# emb.net
KiCad netlist of a schematic drawn in EasyEDA
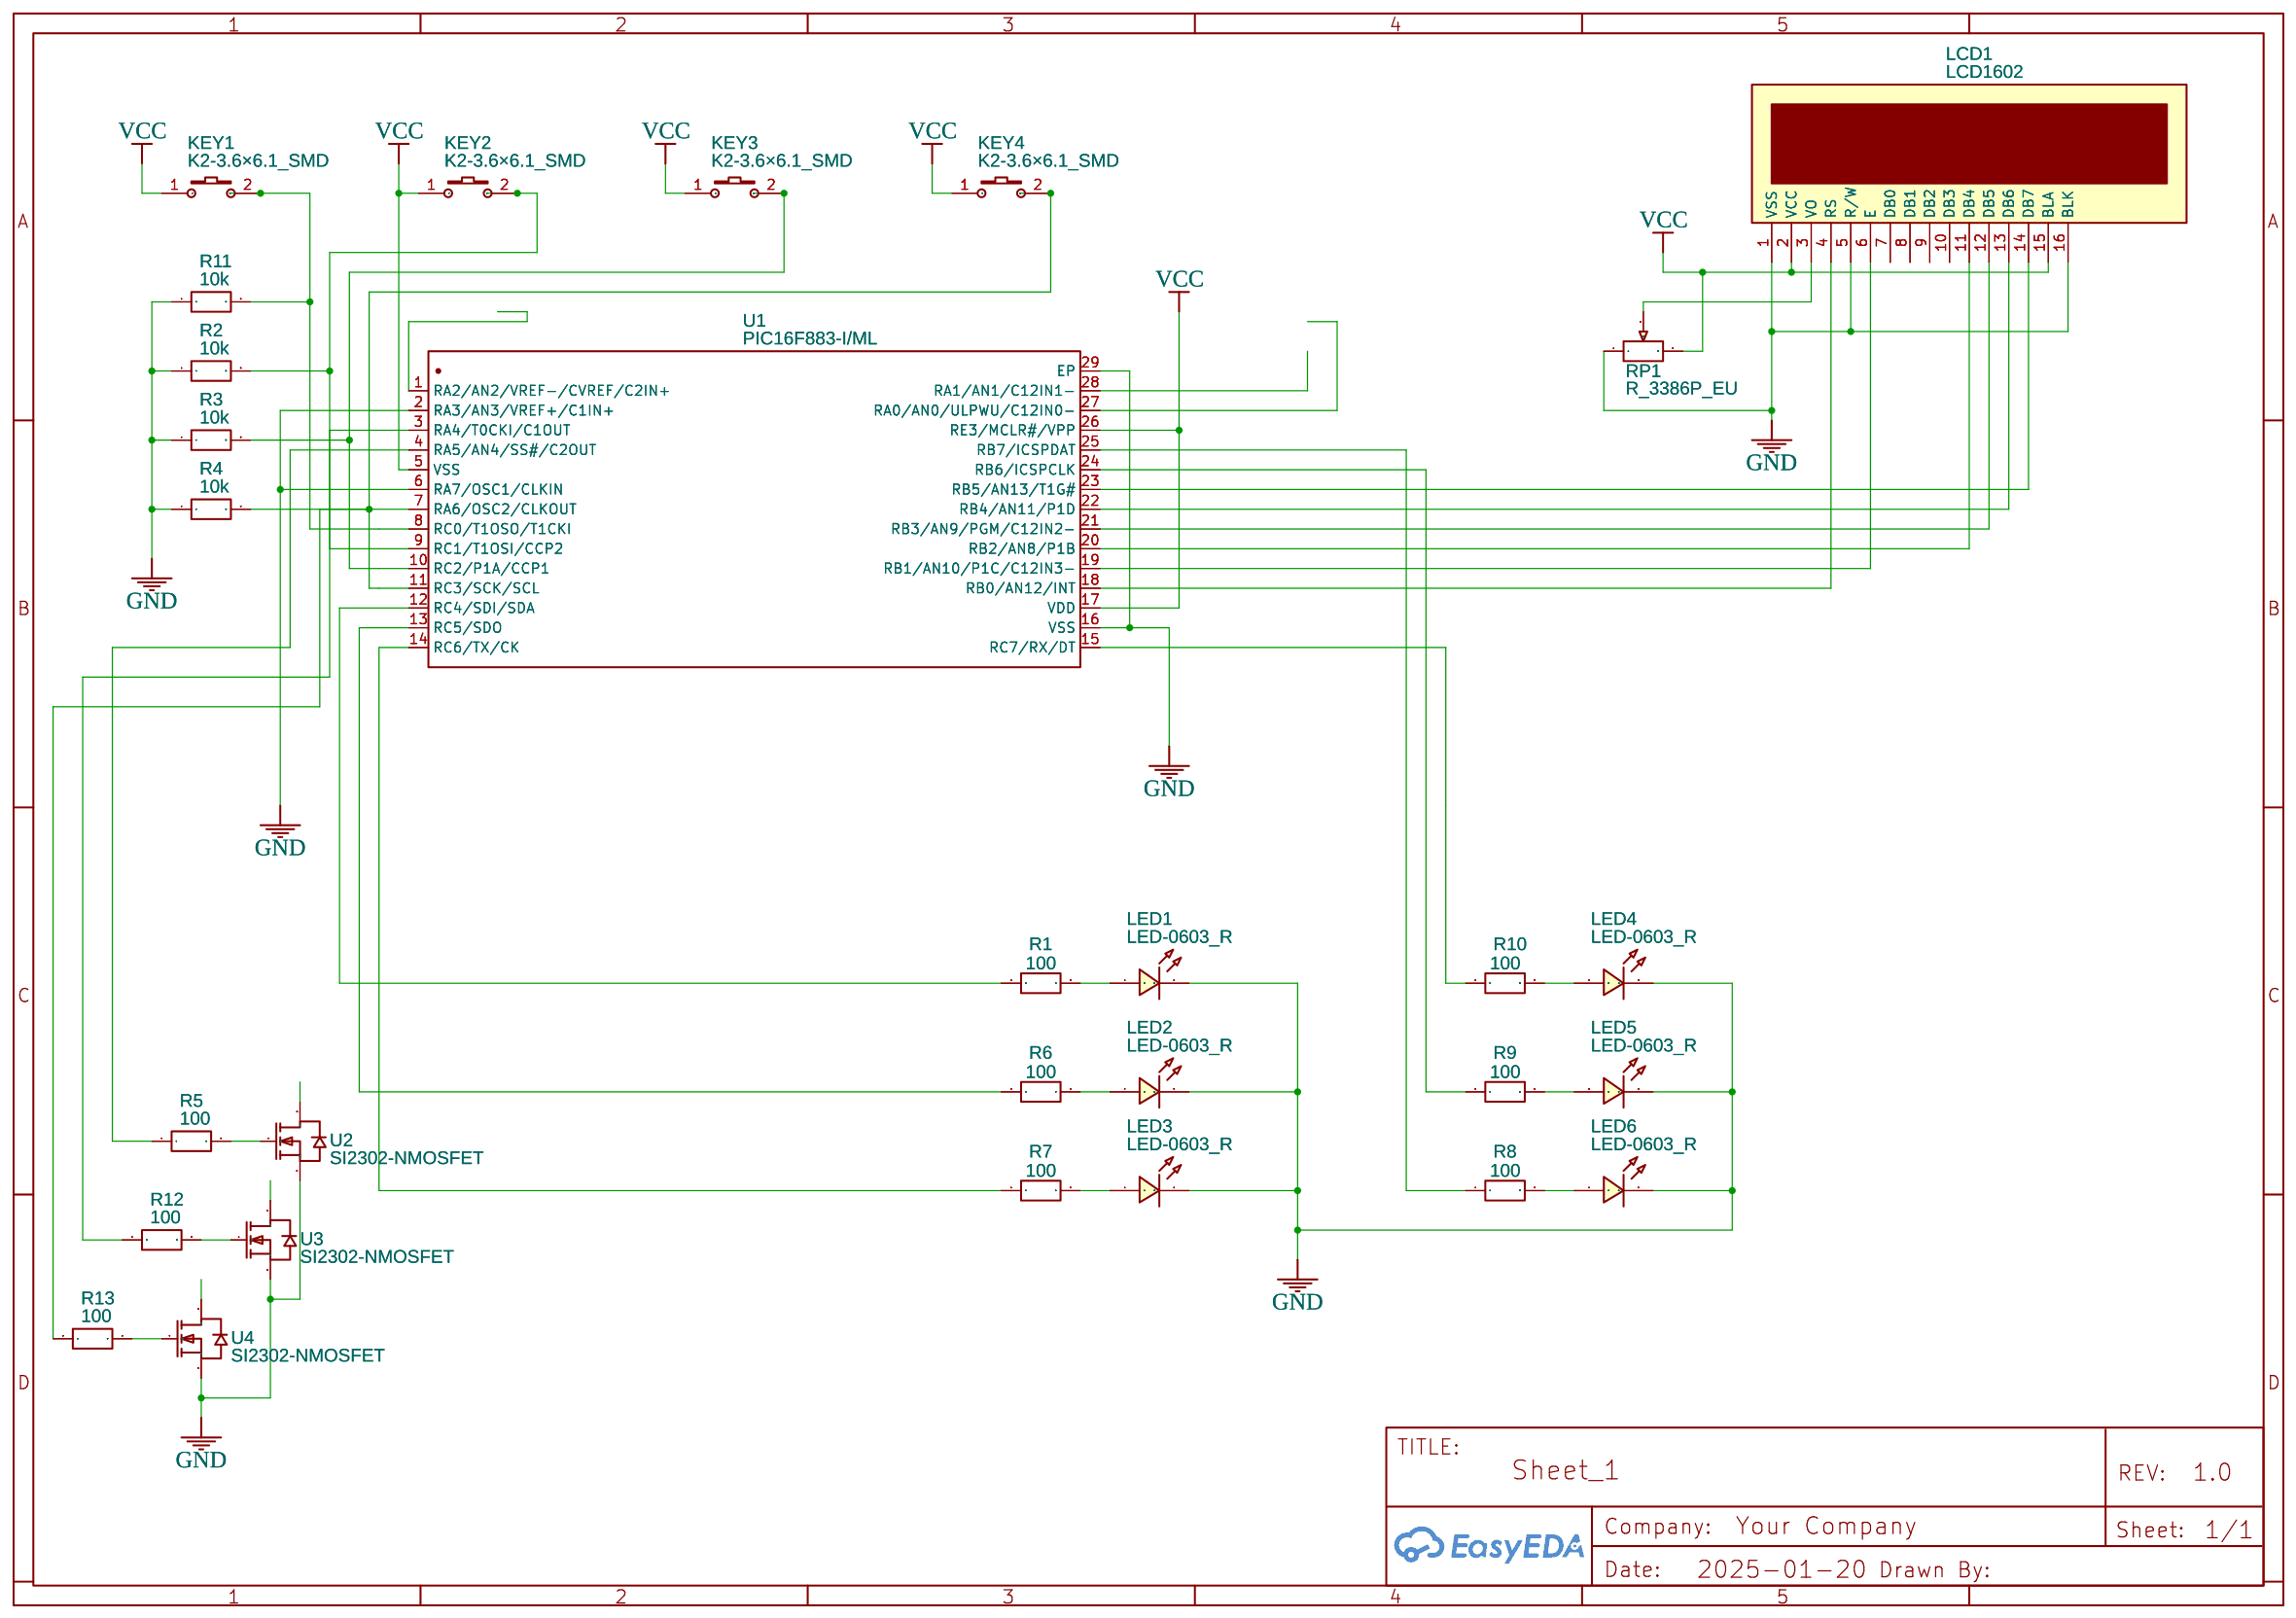
[diagram p0: schematic sheet]

(export (version "E")
  (design (tool "Eeschema 10.0.6"))
  (components
    (comp (ref "KEY1")
      (value "K2-3.6×6.1_SMD")
      (fields (field (name "Manufacturer Part") "K2-1107ST-A4SW-06"))
      (libsource (lib "") (part "K2-3.6×6.1_SMD"))
    )
    (comp (ref "KEY2")
      (value "K2-3.6×6.1_SMD")
      (fields (field (name "Manufacturer Part") "K2-1107ST-A4SW-06"))
      (libsource (lib "") (part "K2-3.6×6.1_SMD"))
    )
    (comp (ref "KEY3")
      (value "K2-3.6×6.1_SMD")
      (fields (field (name "Manufacturer Part") "K2-1107ST-A4SW-06"))
      (libsource (lib "") (part "K2-3.6×6.1_SMD"))
    )
    (comp (ref "KEY4")
      (value "K2-3.6×6.1_SMD")
      (fields (field (name "Manufacturer Part") "K2-1107ST-A4SW-06"))
      (libsource (lib "") (part "K2-3.6×6.1_SMD"))
    )
    (comp (ref "LCD1")
      (value "LCD1602")
      (fields
        (field (name "Manufacturer Part") "LCM1602K-NSW-BBW")
        (field (name "Manufacturer") "LONTECH(厦门龙特)")
      )
      (libsource (lib "") (part "LCD1602"))
    )
    (comp (ref "LED1")
      (value "LED-0603_R")
      (fields
        (field (name "Manufacturer Part") "19-217/R6C-AL1M2VY/3T")
        (field (name "Manufacturer") "EVERLIGHT(台湾亿光)")
      )
      (libsource (lib "") (part "LED-0603_R"))
    )
    (comp (ref "LED2")
      (value "LED-0603_R")
      (fields
        (field (name "Manufacturer Part") "19-217/R6C-AL1M2VY/3T")
        (field (name "Manufacturer") "EVERLIGHT(台湾亿光)")
      )
      (libsource (lib "") (part "LED-0603_R"))
    )
    (comp (ref "LED3")
      (value "LED-0603_R")
      (fields
        (field (name "Manufacturer Part") "19-217/R6C-AL1M2VY/3T")
        (field (name "Manufacturer") "EVERLIGHT(台湾亿光)")
      )
      (libsource (lib "") (part "LED-0603_R"))
    )
    (comp (ref "LED4")
      (value "LED-0603_R")
      (fields
        (field (name "Manufacturer Part") "19-217/R6C-AL1M2VY/3T")
        (field (name "Manufacturer") "EVERLIGHT(台湾亿光)")
      )
      (libsource (lib "") (part "LED-0603_R"))
    )
    (comp (ref "LED5")
      (value "LED-0603_R")
      (fields
        (field (name "Manufacturer Part") "19-217/R6C-AL1M2VY/3T")
        (field (name "Manufacturer") "EVERLIGHT(台湾亿光)")
      )
      (libsource (lib "") (part "LED-0603_R"))
    )
    (comp (ref "LED6")
      (value "LED-0603_R")
      (fields
        (field (name "Manufacturer Part") "19-217/R6C-AL1M2VY/3T")
        (field (name "Manufacturer") "EVERLIGHT(台湾亿光)")
      )
      (libsource (lib "") (part "LED-0603_R"))
    )
    (comp (ref "R1") (value "100") (libsource (lib "") (part "R_0603_EU")))
    (comp (ref "R2") (value "10k") (libsource (lib "") (part "R_0603_EU")))
    (comp (ref "R3") (value "10k") (libsource (lib "") (part "R_0603_EU")))
    (comp (ref "R4") (value "10k") (libsource (lib "") (part "R_0603_EU")))
    (comp (ref "R5") (value "100") (libsource (lib "") (part "R_0603_EU")))
    (comp (ref "R6") (value "100") (libsource (lib "") (part "R_0603_EU")))
    (comp (ref "R7") (value "100") (libsource (lib "") (part "R_0603_EU")))
    (comp (ref "R8") (value "100") (libsource (lib "") (part "R_0603_EU")))
    (comp (ref "R9") (value "100") (libsource (lib "") (part "R_0603_EU")))
    (comp (ref "R10") (value "100") (libsource (lib "") (part "R_0603_EU")))
    (comp (ref "R11") (value "10k") (libsource (lib "") (part "R_0603_EU")))
    (comp (ref "R12") (value "100") (libsource (lib "") (part "R_0603_EU")))
    (comp (ref "R13") (value "100") (libsource (lib "") (part "R_0603_EU")))
    (comp (ref "RP1") (value "R_3386P_EU") (libsource (lib "") (part "R_3386P_EU")))
    (comp (ref "U1")
      (value "PIC16F883-I/ML")
      (fields (field (name "Manufacturer") "MICROCHIP(美国微芯)"))
      (libsource (lib "") (part "PIC16F883-I/ML"))
    )
    (comp (ref "U2")
      (value "SI2302-NMOSFET")
      (fields (field (name "Manufacturer Part") "si2302-nmosfet"))
      (libsource (lib "") (part "SI2302-NMOSFET"))
    )
    (comp (ref "U3")
      (value "SI2302-NMOSFET")
      (fields (field (name "Manufacturer Part") "si2302-nmosfet"))
      (libsource (lib "") (part "SI2302-NMOSFET"))
    )
    (comp (ref "U4")
      (value "SI2302-NMOSFET")
      (fields (field (name "Manufacturer Part") "si2302-nmosfet"))
      (libsource (lib "") (part "SI2302-NMOSFET"))
    )
  )
  (nets
    (net (code "1") (name "GND") (class "Default")
      (node (ref "LCD1") (pin "1") (pinfunction "VSS_1") (pintype "unspecified"))
      (node (ref "LCD1") (pin "16") (pinfunction "BLK_16") (pintype "unspecified"))
      (node (ref "LCD1") (pin "5") (pinfunction "R/W_5") (pintype "unspecified"))
      (node (ref "LED1") (pin "2") (pinfunction "2_2") (pintype "unspecified"))
      (node (ref "LED2") (pin "2") (pinfunction "2_2") (pintype "unspecified"))
      (node (ref "LED3") (pin "2") (pinfunction "2_2") (pintype "unspecified"))
      (node (ref "LED4") (pin "2") (pinfunction "2_2") (pintype "unspecified"))
      (node (ref "LED5") (pin "2") (pinfunction "2_2") (pintype "unspecified"))
      (node (ref "LED6") (pin "2") (pinfunction "2_2") (pintype "unspecified"))
      (node (ref "R11") (pin "1") (pinfunction "1_1") (pintype "unspecified"))
      (node (ref "R2") (pin "1") (pinfunction "1_1") (pintype "unspecified"))
      (node (ref "R3") (pin "1") (pinfunction "1_1") (pintype "unspecified"))
      (node (ref "R4") (pin "1") (pinfunction "1_1") (pintype "unspecified"))
      (node (ref "RP1") (pin "1") (pinfunction "1_1") (pintype "input"))
      (node (ref "U1") (pin "16") (pinfunction "VSS_16") (pintype "unspecified"))
      (node (ref "U1") (pin "2") (pinfunction "RA3/AN3/VREF+/C1IN+_2") (pintype "unspecified"))
      (node (ref "U1") (pin "29") (pinfunction "EP_29") (pintype "unspecified"))
      (node (ref "U1") (pin "6") (pinfunction "RA7/OSC1/CLKIN_6") (pintype "unspecified"))
      (node (ref "U2") (pin "2") (pinfunction "S_2") (pintype "unspecified"))
      (node (ref "U3") (pin "2") (pinfunction "S_2") (pintype "unspecified"))
      (node (ref "U4") (pin "2") (pinfunction "S_2") (pintype "unspecified"))
    )
    (net (code "2") (name "Net-(LCD1-DB4)") (class "Default")
      (node (ref "LCD1") (pin "11") (pinfunction "DB4_11") (pintype "unspecified"))
      (node (ref "U1") (pin "20") (pinfunction "RB2/AN8/P1B_20") (pintype "unspecified"))
    )
    (net (code "3") (name "Net-(LCD1-DB5)") (class "Default")
      (node (ref "LCD1") (pin "12") (pinfunction "DB5_12") (pintype "unspecified"))
      (node (ref "U1") (pin "21") (pinfunction "RB3/AN9/PGM/C12IN2-_21") (pintype "unspecified"))
    )
    (net (code "4") (name "Net-(LCD1-DB6)") (class "Default")
      (node (ref "LCD1") (pin "13") (pinfunction "DB6_13") (pintype "unspecified"))
      (node (ref "U1") (pin "22") (pinfunction "RB4/AN11/P1D_22") (pintype "unspecified"))
    )
    (net (code "5") (name "Net-(LCD1-DB7)") (class "Default")
      (node (ref "LCD1") (pin "14") (pinfunction "DB7_14") (pintype "unspecified"))
      (node (ref "U1") (pin "23") (pinfunction "RB5/AN13/T1G#_23") (pintype "unspecified"))
    )
    (net (code "6") (name "Net-(LCD1-E)") (class "Default")
      (node (ref "LCD1") (pin "6") (pinfunction "E_6") (pintype "unspecified"))
      (node (ref "U1") (pin "19") (pinfunction "RB1/AN10/P1C/C12IN3-_19") (pintype "unspecified"))
    )
    (net (code "7") (name "Net-(LCD1-RS)") (class "Default")
      (node (ref "LCD1") (pin "4") (pinfunction "RS_4") (pintype "unspecified"))
      (node (ref "U1") (pin "18") (pinfunction "RB0/AN12/INT_18") (pintype "unspecified"))
    )
    (net (code "8") (name "Net-(LCD1-VO)") (class "Default")
      (node (ref "LCD1") (pin "3") (pinfunction "VO_3") (pintype "unspecified"))
      (node (ref "RP1") (pin "2") (pinfunction "2_2") (pintype "input"))
    )
    (net (code "9") (name "Net-(LED1-Pad1)") (class "Default")
      (node (ref "LED1") (pin "1") (pinfunction "1_1") (pintype "unspecified"))
      (node (ref "R1") (pin "2") (pinfunction "2_2") (pintype "unspecified"))
    )
    (net (code "10") (name "Net-(LED2-Pad1)") (class "Default")
      (node (ref "LED2") (pin "1") (pinfunction "1_1") (pintype "unspecified"))
      (node (ref "R6") (pin "2") (pinfunction "2_2") (pintype "unspecified"))
    )
    (net (code "11") (name "Net-(LED3-Pad1)") (class "Default")
      (node (ref "LED3") (pin "1") (pinfunction "1_1") (pintype "unspecified"))
      (node (ref "R7") (pin "2") (pinfunction "2_2") (pintype "unspecified"))
    )
    (net (code "12") (name "Net-(LED4-Pad1)") (class "Default")
      (node (ref "LED4") (pin "1") (pinfunction "1_1") (pintype "unspecified"))
      (node (ref "R10") (pin "2") (pinfunction "2_2") (pintype "unspecified"))
    )
    (net (code "13") (name "Net-(LED5-Pad1)") (class "Default")
      (node (ref "LED5") (pin "1") (pinfunction "1_1") (pintype "unspecified"))
      (node (ref "R9") (pin "2") (pinfunction "2_2") (pintype "unspecified"))
    )
    (net (code "14") (name "Net-(LED6-Pad1)") (class "Default")
      (node (ref "LED6") (pin "1") (pinfunction "1_1") (pintype "unspecified"))
      (node (ref "R8") (pin "2") (pinfunction "2_2") (pintype "unspecified"))
    )
    (net (code "15") (name "Net-(U1-RA4{slash}T0CKI{slash}C1OUT)") (class "Default")
      (node (ref "R12") (pin "1") (pinfunction "1_1") (pintype "unspecified"))
      (node (ref "U1") (pin "3") (pinfunction "RA4/T0CKI/C1OUT_3") (pintype "unspecified"))
    )
    (net (code "16") (name "Net-(U1-RA5{slash}AN4{slash}SS#{slash}C2OUT)") (class "Default")
      (node (ref "R5") (pin "1") (pinfunction "1_1") (pintype "unspecified"))
      (node (ref "U1") (pin "4") (pinfunction "RA5/AN4/SS#/C2OUT_4") (pintype "unspecified"))
    )
    (net (code "17") (name "Net-(U1-RA6{slash}OSC2{slash}CLKOUT)") (class "Default")
      (node (ref "KEY4") (pin "2") (pinfunction "2_2") (pintype "unspecified"))
      (node (ref "R13") (pin "1") (pinfunction "1_1") (pintype "unspecified"))
      (node (ref "R4") (pin "2") (pinfunction "2_2") (pintype "unspecified"))
      (node (ref "U1") (pin "11") (pinfunction "RC3/SCK/SCL_11") (pintype "unspecified"))
      (node (ref "U1") (pin "7") (pinfunction "RA6/OSC2/CLKOUT_7") (pintype "unspecified"))
    )
    (net (code "18") (name "Net-(U1-RB6{slash}ICSPCLK)") (class "Default")
      (node (ref "R9") (pin "1") (pinfunction "1_1") (pintype "unspecified"))
      (node (ref "U1") (pin "24") (pinfunction "RB6/ICSPCLK_24") (pintype "unspecified"))
    )
    (net (code "19") (name "Net-(U1-RB7{slash}ICSPDAT)") (class "Default")
      (node (ref "R8") (pin "1") (pinfunction "1_1") (pintype "unspecified"))
      (node (ref "U1") (pin "25") (pinfunction "RB7/ICSPDAT_25") (pintype "unspecified"))
    )
    (net (code "20") (name "Net-(U1-RC0{slash}T1OSO{slash}T1CKI)") (class "Default")
      (node (ref "KEY1") (pin "2") (pinfunction "2_2") (pintype "unspecified"))
      (node (ref "R11") (pin "2") (pinfunction "2_2") (pintype "unspecified"))
      (node (ref "U1") (pin "8") (pinfunction "RC0/T1OSO/T1CKI_8") (pintype "unspecified"))
    )
    (net (code "21") (name "Net-(U1-RC1{slash}T1OSI{slash}CCP2)") (class "Default")
      (node (ref "KEY2") (pin "2") (pinfunction "2_2") (pintype "unspecified"))
      (node (ref "R2") (pin "2") (pinfunction "2_2") (pintype "unspecified"))
      (node (ref "U1") (pin "9") (pinfunction "RC1/T1OSI/CCP2_9") (pintype "unspecified"))
    )
    (net (code "22") (name "Net-(U1-RC2{slash}P1A{slash}CCP1)") (class "Default")
      (node (ref "KEY3") (pin "2") (pinfunction "2_2") (pintype "unspecified"))
      (node (ref "R3") (pin "2") (pinfunction "2_2") (pintype "unspecified"))
      (node (ref "U1") (pin "10") (pinfunction "RC2/P1A/CCP1_10") (pintype "unspecified"))
    )
    (net (code "23") (name "Net-(U1-RC4{slash}SDI{slash}SDA)") (class "Default")
      (node (ref "R1") (pin "1") (pinfunction "1_1") (pintype "unspecified"))
      (node (ref "U1") (pin "12") (pinfunction "RC4/SDI/SDA_12") (pintype "unspecified"))
    )
    (net (code "24") (name "Net-(U1-RC5{slash}SDO)") (class "Default")
      (node (ref "R6") (pin "1") (pinfunction "1_1") (pintype "unspecified"))
      (node (ref "U1") (pin "13") (pinfunction "RC5/SDO_13") (pintype "unspecified"))
    )
    (net (code "25") (name "Net-(U1-RC6{slash}TX{slash}CK)") (class "Default")
      (node (ref "R7") (pin "1") (pinfunction "1_1") (pintype "unspecified"))
      (node (ref "U1") (pin "14") (pinfunction "RC6/TX/CK_14") (pintype "unspecified"))
    )
    (net (code "26") (name "Net-(U1-RC7{slash}RX{slash}DT)") (class "Default")
      (node (ref "R10") (pin "1") (pinfunction "1_1") (pintype "unspecified"))
      (node (ref "U1") (pin "15") (pinfunction "RC7/RX/DT_15") (pintype "unspecified"))
    )
    (net (code "27") (name "Net-(U2-G)") (class "Default")
      (node (ref "R5") (pin "2") (pinfunction "2_2") (pintype "unspecified"))
      (node (ref "U2") (pin "1") (pinfunction "G_1") (pintype "unspecified"))
    )
    (net (code "28") (name "Net-(U3-G)") (class "Default")
      (node (ref "R12") (pin "2") (pinfunction "2_2") (pintype "unspecified"))
      (node (ref "U3") (pin "1") (pinfunction "G_1") (pintype "unspecified"))
    )
    (net (code "29") (name "Net-(U4-G)") (class "Default")
      (node (ref "R13") (pin "2") (pinfunction "2_2") (pintype "unspecified"))
      (node (ref "U4") (pin "1") (pinfunction "G_1") (pintype "unspecified"))
    )
    (net (code "30") (name "VCC") (class "Default")
      (node (ref "KEY1") (pin "1") (pinfunction "1_1") (pintype "unspecified"))
      (node (ref "KEY2") (pin "1") (pinfunction "1_1") (pintype "unspecified"))
      (node (ref "KEY3") (pin "1") (pinfunction "1_1") (pintype "unspecified"))
      (node (ref "KEY4") (pin "1") (pinfunction "1_1") (pintype "unspecified"))
      (node (ref "LCD1") (pin "15") (pinfunction "BLA_15") (pintype "unspecified"))
      (node (ref "LCD1") (pin "2") (pinfunction "VCC_2") (pintype "unspecified"))
      (node (ref "RP1") (pin "3") (pinfunction "3_3") (pintype "input"))
      (node (ref "U1") (pin "17") (pinfunction "VDD_17") (pintype "unspecified"))
      (node (ref "U1") (pin "26") (pinfunction "RE3/MCLR#/VPP_26") (pintype "unspecified"))
      (node (ref "U1") (pin "5") (pinfunction "VSS_5") (pintype "unspecified"))
    )
    (net (code "31") (name "unconnected-(LCD1-DB0-Pad7)") (class "Default")
      (node (ref "LCD1") (pin "7") (pinfunction "DB0_7") (pintype "unspecified"))
    )
    (net (code "32") (name "unconnected-(LCD1-DB1-Pad8)") (class "Default")
      (node (ref "LCD1") (pin "8") (pinfunction "DB1_8") (pintype "unspecified"))
    )
    (net (code "33") (name "unconnected-(LCD1-DB2-Pad9)") (class "Default")
      (node (ref "LCD1") (pin "9") (pinfunction "DB2_9") (pintype "unspecified"))
    )
    (net (code "34") (name "unconnected-(LCD1-DB3-Pad10)") (class "Default")
      (node (ref "LCD1") (pin "10") (pinfunction "DB3_10") (pintype "unspecified"))
    )
    (net (code "35") (name "unconnected-(U1-RA0{slash}AN0{slash}ULPWU{slash}C12IN0--Pad27)") (class "Default")
      (node (ref "U1") (pin "27") (pinfunction "RA0/AN0/ULPWU/C12IN0-_27") (pintype "unspecified"))
    )
    (net (code "36") (name "unconnected-(U1-RA1{slash}AN1{slash}C12IN1--Pad28)") (class "Default")
      (node (ref "U1") (pin "28") (pinfunction "RA1/AN1/C12IN1-_28") (pintype "unspecified"))
    )
    (net (code "37") (name "unconnected-(U1-RA2{slash}AN2{slash}VREF-{slash}CVREF{slash}C2IN+-Pad1)") (class "Default")
      (node (ref "U1") (pin "1") (pinfunction "RA2/AN2/VREF-/CVREF/C2IN+_1") (pintype "unspecified"))
    )
    (net (code "38") (name "unconnected-(U2-D-Pad3)") (class "Default")
      (node (ref "U2") (pin "3") (pinfunction "D_3") (pintype "unspecified"))
    )
    (net (code "39") (name "unconnected-(U3-D-Pad3)") (class "Default")
      (node (ref "U3") (pin "3") (pinfunction "D_3") (pintype "unspecified"))
    )
    (net (code "40") (name "unconnected-(U4-D-Pad3)") (class "Default")
      (node (ref "U4") (pin "3") (pinfunction "D_3") (pintype "unspecified"))
    )
  )
)
